# VDD_div.net
KiCad netlist of a schematic drawn in Altium Designer
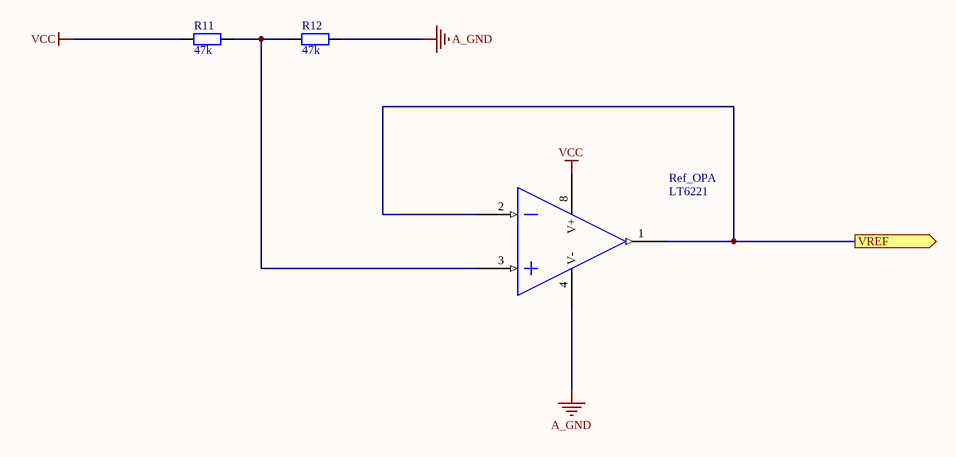
[diagram p0: VDD_div.SchDoc]

(export (version "E")
  (design (tool "Eeschema 10.0.6"))
  (components
    (comp (ref "R11") (value "47k") (description "Resistor") (libsource (lib "EceParts") (part "Resistor")))
    (comp (ref "R12") (value "47k") (description "Resistor") (libsource (lib "EceParts") (part "Resistor")))
    (comp (ref "Ref_OP") (value "LT6221") (libsource (lib "EceParts") (part "LT6221")))
  )
  (nets
    (net (code "1") (name "/VREF") (class "Default")
      (node (ref "Ref_OP") (pin "1") (pinfunction "OUT1_1") (pintype "output"))
      (node (ref "Ref_OP") (pin "2") (pinfunction "IN1(-)_2") (pintype "input"))
    )
    (net (code "2") (name "A_GND") (class "Default")
      (node (ref "R12") (pin "2") (pinfunction "2_2") (pintype "passive"))
      (node (ref "Ref_OP") (pin "4") (pinfunction "V-_4") (pintype "power_in"))
    )
    (net (code "3") (name "Net-(Ref_OPA-IN1(+))") (class "Default")
      (node (ref "R11") (pin "2") (pinfunction "2_2") (pintype "passive"))
      (node (ref "R12") (pin "1") (pinfunction "1_1") (pintype "passive"))
      (node (ref "Ref_OP") (pin "3") (pinfunction "IN1(+)_3") (pintype "input"))
    )
    (net (code "4") (name "VCC") (class "Default")
      (node (ref "R11") (pin "1") (pinfunction "1_1") (pintype "passive"))
      (node (ref "Ref_OP") (pin "8") (pinfunction "V+_8") (pintype "power_in"))
    )
  )
)
